# RF.net
KiCad netlist of a schematic drawn in Altium Designer
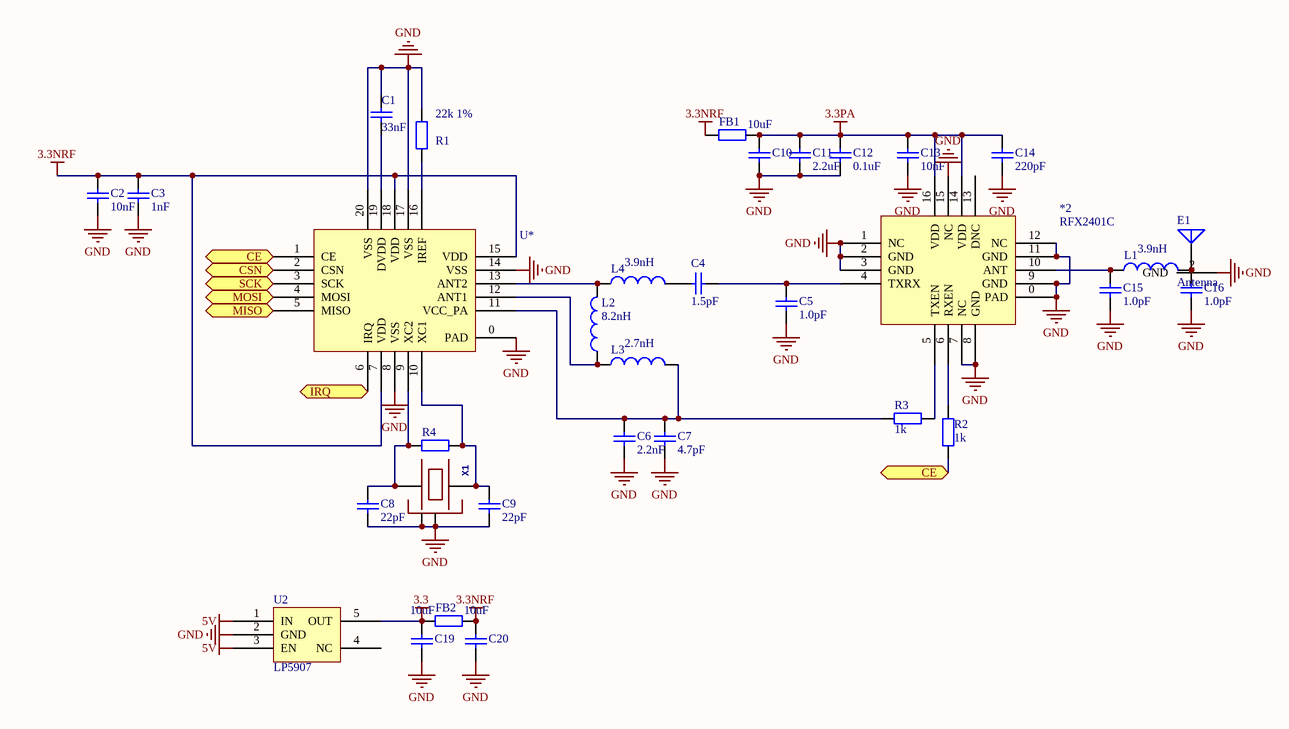
[diagram p0: RF.SchDoc]

(export (version "E")
  (design (tool "Eeschema 10.0.6"))
  (components
    (comp (ref "*2")
      (value "RFX2401C")
      (footprint "RFX2401C")
      (libsource (lib "NRF24L01_PA") (part "RFX2401C"))
    )
    (comp (ref "C1")
      (value "33nF")
      (footprint "0402")
      (description "Capacitor")
      (fields (field (name "Comment") "Cap") (field (name "PUBLISHER") "Altium Limited"))
      (libsource (lib "RTC6705") (part "Cap"))
    )
    (comp (ref "C2")
      (value "10nF")
      (footprint "0402")
      (description "Capacitor")
      (fields (field (name "Comment") "Cap") (field (name "PUBLISHER") "Altium Limited"))
      (libsource (lib "RTC6705") (part "Cap"))
    )
    (comp (ref "C3")
      (value "1nF")
      (footprint "0402")
      (description "Capacitor")
      (fields (field (name "Comment") "Cap") (field (name "PUBLISHER") "Altium Limited"))
      (libsource (lib "RTC6705") (part "Cap"))
    )
    (comp (ref "C4")
      (value "1.5pF")
      (footprint "0402")
      (description "Capacitor")
      (fields (field (name "Comment") "Cap") (field (name "PUBLISHER") "Altium Limited"))
      (libsource (lib "RTC6705") (part "Cap"))
    )
    (comp (ref "C5")
      (value "1.0pF")
      (footprint "0402")
      (description "Capacitor")
      (fields (field (name "Comment") "Cap") (field (name "PUBLISHER") "Altium Limited"))
      (libsource (lib "RTC6705") (part "Cap"))
    )
    (comp (ref "C6")
      (value "2.2nF")
      (footprint "0402")
      (description "Capacitor")
      (fields (field (name "Comment") "Cap") (field (name "PUBLISHER") "Altium Limited"))
      (libsource (lib "RTC6705") (part "Cap"))
    )
    (comp (ref "C7")
      (value "4.7pF")
      (footprint "0402")
      (description "Capacitor")
      (fields (field (name "Comment") "Cap") (field (name "PUBLISHER") "Altium Limited"))
      (libsource (lib "RTC6705") (part "Cap"))
    )
    (comp (ref "C8")
      (value "22pF")
      (footprint "0402")
      (description "Capacitor")
      (fields (field (name "Comment") "Cap") (field (name "PUBLISHER") "Altium Limited"))
      (libsource (lib "RTC6705") (part "Cap"))
    )
    (comp (ref "C9")
      (value "22pF")
      (footprint "0402")
      (description "Capacitor")
      (fields (field (name "Comment") "Cap") (field (name "PUBLISHER") "Altium Limited"))
      (libsource (lib "RTC6705") (part "Cap"))
    )
    (comp (ref "C10")
      (value "10uF")
      (footprint "0603")
      (description "Capacitor")
      (fields (field (name "PUBLISHER") "Altium Limited"))
      (libsource (lib "RTC6705") (part "Cap"))
    )
    (comp (ref "C11")
      (value "2.2uF")
      (footprint "0402")
      (description "Capacitor")
      (fields (field (name "Comment") "Cap") (field (name "PUBLISHER") "Altium Limited"))
      (libsource (lib "RTC6705") (part "Cap"))
    )
    (comp (ref "C12")
      (value "0.1uF")
      (footprint "0402")
      (description "Capacitor")
      (fields (field (name "Comment") "Cap") (field (name "PUBLISHER") "Altium Limited"))
      (libsource (lib "RTC6705") (part "Cap"))
    )
    (comp (ref "C13")
      (value "10nF")
      (footprint "0402")
      (description "Capacitor")
      (fields (field (name "Comment") "Cap") (field (name "PUBLISHER") "Altium Limited"))
      (libsource (lib "RTC6705") (part "Cap"))
    )
    (comp (ref "C14")
      (value "220pF")
      (footprint "0402")
      (description "Capacitor")
      (fields (field (name "Comment") "Cap") (field (name "PUBLISHER") "Altium Limited"))
      (libsource (lib "RTC6705") (part "Cap"))
    )
    (comp (ref "C15")
      (value "1.0pF")
      (footprint "0402")
      (description "Capacitor")
      (fields (field (name "Comment") "Cap") (field (name "PUBLISHER") "Altium Limited"))
      (libsource (lib "RTC6705") (part "Cap"))
    )
    (comp (ref "C16")
      (value "1.0pF")
      (footprint "0402")
      (description "Capacitor")
      (fields (field (name "Comment") "Cap") (field (name "PUBLISHER") "Altium Limited"))
      (libsource (lib "RTC6705") (part "Cap"))
    )
    (comp (ref "C19")
      (value "10uF")
      (footprint "0603")
      (description "Capacitor")
      (fields (field (name "PUBLISHER") "Altium Limited"))
      (libsource (lib "RTC6705") (part "Cap"))
    )
    (comp (ref "C20")
      (value "10uF")
      (footprint "0603")
      (description "Capacitor")
      (fields (field (name "PUBLISHER") "Altium Limited"))
      (libsource (lib "RTC6705") (part "Cap"))
    )
    (comp (ref "E1")
      (value "Antenna")
      (footprint "IPEX")
      (description "Generic Antenna")
      (fields (field (name "PUBLISHER") "Altium Limited"))
      (libsource (lib "Miscellaneous Devices") (part "Antenna"))
    )
    (comp (ref "FB1")
      (value "FB")
      (footprint "0402")
      (description "Resistor")
      (fields (field (name "PUBLISHER") "Altium Limited"))
      (libsource (lib "RTC6705") (part "Res2"))
    )
    (comp (ref "FB2")
      (value "FB")
      (footprint "0402")
      (description "Resistor")
      (fields (field (name "PUBLISHER") "Altium Limited"))
      (libsource (lib "RTC6705") (part "Res2"))
    )
    (comp (ref "L1")
      (value "3.9nH")
      (footprint "0402")
      (description "Inductor")
      (fields (field (name "PUBLISHER") "Altium Limited"))
      (libsource (lib "Miscellaneous Devices") (part "Inductor"))
    )
    (comp (ref "L2")
      (value "8.2nH")
      (footprint "0402")
      (description "Inductor")
      (fields (field (name "PUBLISHER") "Altium Limited"))
      (libsource (lib "Miscellaneous Devices") (part "Inductor"))
    )
    (comp (ref "L3")
      (value "2.7nH")
      (footprint "0402")
      (description "Inductor")
      (fields (field (name "PUBLISHER") "Altium Limited"))
      (libsource (lib "Miscellaneous Devices") (part "Inductor"))
    )
    (comp (ref "L4")
      (value "3.9nH")
      (footprint "0402")
      (description "Inductor")
      (fields (field (name "PUBLISHER") "Altium Limited"))
      (libsource (lib "Miscellaneous Devices") (part "Inductor"))
    )
    (comp (ref "R1")
      (value "22k 1%")
      (footprint "0402")
      (description "Resistor")
      (fields (field (name "Comment") "Res2") (field (name "PUBLISHER") "Altium Limited"))
      (libsource (lib "") (part "Res2_1"))
    )
    (comp (ref "R2")
      (value "1k")
      (footprint "0402")
      (description "Resistor")
      (fields (field (name "Comment") "Res2") (field (name "PUBLISHER") "Altium Limited"))
      (libsource (lib "") (part "Res2_2"))
    )
    (comp (ref "R3")
      (value "1k")
      (footprint "0402")
      (description "Resistor")
      (fields (field (name "Comment") "Res2") (field (name "PUBLISHER") "Altium Limited"))
      (libsource (lib "RTC6705") (part "Res2"))
    )
    (comp (ref "R4")
      (value "1M")
      (footprint "0402")
      (description "Resistor")
      (fields (field (name "PUBLISHER") "Altium Limited"))
      (libsource (lib "RTC6705") (part "Res2"))
    )
    (comp (ref "U*")
      (value "NRF24L01")
      (footprint "NRF24L01")
      (libsource (lib "NRF24L01_PA") (part "NRF24L01"))
    )
    (comp (ref "U2") (value "LP5907") (footprint "SOT23-5") (libsource (lib "RTC6705") (part "LP5907")))
    (comp (ref "X1")
      (value "16Mhz")
      (footprint "OSCILLATOR-3.2X2.5")
      (description "Crystal Oscillator in 3.2x2.5 SMD")
      (libsource (lib "pixhawk2") (part "OSCILLATOR-3.2X2.5"))
    )
  )
  (nets
    (net (code "1") (name "/CE") (class "Default")
      (node (ref "R2") (pin "1") (pinfunction "1_1") (pintype "passive"))
      (node (ref "U*") (pin "1") (pinfunction "CE_1") (pintype "passive"))
    )
    (net (code "2") (name "/CSN") (class "Default")
      (node (ref "U*") (pin "2") (pinfunction "CSN_2") (pintype "passive"))
    )
    (net (code "3") (name "/IRQ") (class "Default")
      (node (ref "U*") (pin "6") (pinfunction "IRQ_6") (pintype "passive"))
    )
    (net (code "4") (name "/MISO") (class "Default")
      (node (ref "U*") (pin "5") (pinfunction "MISO_5") (pintype "passive"))
    )
    (net (code "5") (name "/MOSI") (class "Default")
      (node (ref "U*") (pin "4") (pinfunction "MOSI_4") (pintype "passive"))
    )
    (net (code "6") (name "/SCK") (class "Default")
      (node (ref "U*") (pin "3") (pinfunction "SCK_3") (pintype "passive"))
    )
    (net (code "7") (name "3.3") (class "Default")
      (node (ref "C19") (pin "1") (pinfunction "1_1") (pintype "passive"))
      (node (ref "FB2") (pin "1") (pinfunction "1_1") (pintype "passive"))
      (node (ref "U2") (pin "5") (pinfunction "OUT_5") (pintype "passive"))
    )
    (net (code "8") (name "3.3NRF") (class "Default")
      (node (ref "C2") (pin "1") (pinfunction "1_1") (pintype "passive"))
      (node (ref "C20") (pin "1") (pinfunction "1_1") (pintype "passive"))
      (node (ref "C3") (pin "1") (pinfunction "1_1") (pintype "passive"))
      (node (ref "FB1") (pin "1") (pinfunction "1_1") (pintype "passive"))
      (node (ref "FB2") (pin "2") (pinfunction "2_2") (pintype "passive"))
      (node (ref "U*") (pin "15") (pinfunction "VDD_15") (pintype "passive"))
      (node (ref "U*") (pin "18") (pinfunction "VDD_18") (pintype "passive"))
      (node (ref "U*") (pin "7") (pinfunction "VDD_7") (pintype "passive"))
    )
    (net (code "9") (name "3.3PA") (class "Default")
      (node (ref "*2") (pin "14") (pinfunction "VDD_14") (pintype "passive"))
      (node (ref "*2") (pin "16") (pinfunction "VDD_16") (pintype "passive"))
      (node (ref "C10") (pin "1") (pinfunction "1_1") (pintype "passive"))
      (node (ref "C11") (pin "1") (pinfunction "1_1") (pintype "passive"))
      (node (ref "C12") (pin "1") (pinfunction "1_1") (pintype "passive"))
      (node (ref "C13") (pin "1") (pinfunction "1_1") (pintype "passive"))
      (node (ref "C14") (pin "1") (pinfunction "1_1") (pintype "passive"))
      (node (ref "FB1") (pin "2") (pinfunction "2_2") (pintype "passive"))
    )
    (net (code "10") (name "5V") (class "Default")
      (node (ref "U2") (pin "1") (pinfunction "IN_1") (pintype "passive"))
      (node (ref "U2") (pin "3") (pinfunction "EN_3") (pintype "passive"))
    )
    (net (code "11") (name "GND") (class "Default")
      (node (ref "*2") (pin "0") (pinfunction "PAD_0") (pintype "passive"))
      (node (ref "*2") (pin "1") (pinfunction "NC_1") (pintype "passive"))
      (node (ref "*2") (pin "11") (pinfunction "GND_11") (pintype "passive"))
      (node (ref "*2") (pin "12") (pinfunction "NC_12") (pintype "passive"))
      (node (ref "*2") (pin "15") (pinfunction "NC_15") (pintype "passive"))
      (node (ref "*2") (pin "2") (pinfunction "GND_2") (pintype "passive"))
      (node (ref "*2") (pin "3") (pinfunction "GND_3") (pintype "passive"))
      (node (ref "*2") (pin "7") (pinfunction "NC_7") (pintype "passive"))
      (node (ref "*2") (pin "8") (pinfunction "GND_8") (pintype "passive"))
      (node (ref "*2") (pin "9") (pinfunction "GND_9") (pintype "passive"))
      (node (ref "C1") (pin "1") (pinfunction "1_1") (pintype "passive"))
      (node (ref "C10") (pin "2") (pinfunction "2_2") (pintype "passive"))
      (node (ref "C11") (pin "2") (pinfunction "2_2") (pintype "passive"))
      (node (ref "C12") (pin "2") (pinfunction "2_2") (pintype "passive"))
      (node (ref "C13") (pin "2") (pinfunction "2_2") (pintype "passive"))
      (node (ref "C14") (pin "2") (pinfunction "2_2") (pintype "passive"))
      (node (ref "C15") (pin "2") (pinfunction "2_2") (pintype "passive"))
      (node (ref "C16") (pin "2") (pinfunction "2_2") (pintype "passive"))
      (node (ref "C19") (pin "2") (pinfunction "2_2") (pintype "passive"))
      (node (ref "C2") (pin "2") (pinfunction "2_2") (pintype "passive"))
      (node (ref "C20") (pin "2") (pinfunction "2_2") (pintype "passive"))
      (node (ref "C3") (pin "2") (pinfunction "2_2") (pintype "passive"))
      (node (ref "C5") (pin "2") (pinfunction "2_2") (pintype "passive"))
      (node (ref "C6") (pin "2") (pinfunction "2_2") (pintype "passive"))
      (node (ref "C7") (pin "2") (pinfunction "2_2") (pintype "passive"))
      (node (ref "C8") (pin "2") (pinfunction "2_2") (pintype "passive"))
      (node (ref "C9") (pin "2") (pinfunction "2_2") (pintype "passive"))
      (node (ref "E1") (pin "2") (pinfunction "GND_2") (pintype "passive"))
      (node (ref "R1") (pin "1") (pinfunction "1_1") (pintype "passive"))
      (node (ref "U*") (pin "0") (pinfunction "PAD_0") (pintype "passive"))
      (node (ref "U*") (pin "14") (pinfunction "VSS_14") (pintype "passive"))
      (node (ref "U*") (pin "17") (pinfunction "VSS_17") (pintype "passive"))
      (node (ref "U*") (pin "20") (pinfunction "VSS_20") (pintype "passive"))
      (node (ref "U*") (pin "8") (pinfunction "VSS_8") (pintype "passive"))
      (node (ref "U2") (pin "2") (pinfunction "GND_2") (pintype "passive"))
      (node (ref "X1") (pin "2") (pinfunction "NC_2_2") (pintype "open_emitter"))
      (node (ref "X1") (pin "4") (pinfunction "NC_4_4") (pintype "open_emitter"))
    )
    (net (code "12") (name "Net-(*2-ANT)") (class "Default")
      (node (ref "*2") (pin "10") (pinfunction "ANT_10") (pintype "passive"))
      (node (ref "C15") (pin "1") (pinfunction "1_1") (pintype "passive"))
      (node (ref "L1") (pin "1") (pinfunction "1_1") (pintype "passive"))
    )
    (net (code "13") (name "Net-(*2-RXEN)") (class "Default")
      (node (ref "*2") (pin "6") (pinfunction "RXEN_6") (pintype "passive"))
      (node (ref "R2") (pin "2") (pinfunction "2_2") (pintype "passive"))
    )
    (net (code "14") (name "Net-(*2-TXEN)") (class "Default")
      (node (ref "*2") (pin "5") (pinfunction "TXEN_5") (pintype "passive"))
      (node (ref "R3") (pin "2") (pinfunction "2_2") (pintype "passive"))
    )
    (net (code "15") (name "Net-(*2-TXRX)") (class "Default")
      (node (ref "*2") (pin "4") (pinfunction "TXRX_4") (pintype "passive"))
      (node (ref "C4") (pin "2") (pinfunction "2_2") (pintype "passive"))
      (node (ref "C5") (pin "1") (pinfunction "1_1") (pintype "passive"))
    )
    (net (code "16") (name "Net-(C4-Pad1)") (class "Default")
      (node (ref "C4") (pin "1") (pinfunction "1_1") (pintype "passive"))
      (node (ref "L4") (pin "2") (pinfunction "2_2") (pintype "passive"))
    )
    (net (code "17") (name "Net-(E1-ANT)") (class "Default")
      (node (ref "C16") (pin "1") (pinfunction "1_1") (pintype "passive"))
      (node (ref "E1") (pin "1") (pinfunction "ANT_1") (pintype "passive"))
      (node (ref "L1") (pin "2") (pinfunction "2_2") (pintype "passive"))
    )
    (net (code "18") (name "Net-(U*-ANT1)") (class "Default")
      (node (ref "L2") (pin "1") (pinfunction "1_1") (pintype "passive"))
      (node (ref "L3") (pin "1") (pinfunction "1_1") (pintype "passive"))
      (node (ref "U*") (pin "12") (pinfunction "ANT1_12") (pintype "passive"))
    )
    (net (code "19") (name "Net-(U*-ANT2)") (class "Default")
      (node (ref "L2") (pin "2") (pinfunction "2_2") (pintype "passive"))
      (node (ref "L4") (pin "1") (pinfunction "1_1") (pintype "passive"))
      (node (ref "U*") (pin "13") (pinfunction "ANT2_13") (pintype "passive"))
    )
    (net (code "20") (name "Net-(U*-DVDD)") (class "Default")
      (node (ref "C1") (pin "2") (pinfunction "2_2") (pintype "passive"))
      (node (ref "U*") (pin "19") (pinfunction "DVDD_19") (pintype "passive"))
    )
    (net (code "21") (name "Net-(U*-IREF)") (class "Default")
      (node (ref "R1") (pin "2") (pinfunction "2_2") (pintype "passive"))
      (node (ref "U*") (pin "16") (pinfunction "IREF_16") (pintype "passive"))
    )
    (net (code "22") (name "Net-(U*-VCC_PA)") (class "Default")
      (node (ref "C6") (pin "1") (pinfunction "1_1") (pintype "passive"))
      (node (ref "C7") (pin "1") (pinfunction "1_1") (pintype "passive"))
      (node (ref "L3") (pin "2") (pinfunction "2_2") (pintype "passive"))
      (node (ref "R3") (pin "1") (pinfunction "1_1") (pintype "passive"))
      (node (ref "U*") (pin "11") (pinfunction "VCC_PA_11") (pintype "passive"))
    )
    (net (code "23") (name "Net-(U*-XC1)") (class "Default")
      (node (ref "C9") (pin "1") (pinfunction "1_1") (pintype "passive"))
      (node (ref "R4") (pin "2") (pinfunction "2_2") (pintype "passive"))
      (node (ref "U*") (pin "10") (pinfunction "XC1_10") (pintype "passive"))
      (node (ref "X1") (pin "3") (pinfunction "3_3") (pintype "passive"))
    )
    (net (code "24") (name "Net-(U*-XC2)") (class "Default")
      (node (ref "C8") (pin "1") (pinfunction "1_1") (pintype "passive"))
      (node (ref "R4") (pin "1") (pinfunction "1_1") (pintype "passive"))
      (node (ref "U*") (pin "9") (pinfunction "XC2_9") (pintype "passive"))
      (node (ref "X1") (pin "1") (pinfunction "1_1") (pintype "passive"))
    )
    (net (code "25") (name "unconnected-(*2-DNC-Pad13)") (class "Default")
      (node (ref "*2") (pin "13") (pinfunction "DNC_13") (pintype "passive"))
    )
    (net (code "26") (name "unconnected-(U2-NC-Pad4)") (class "Default")
      (node (ref "U2") (pin "4") (pinfunction "NC_4") (pintype "passive"))
    )
  )
)
